# V0p2_Main_PCB2.net
KiCad netlist of a schematic drawn in EAGLE
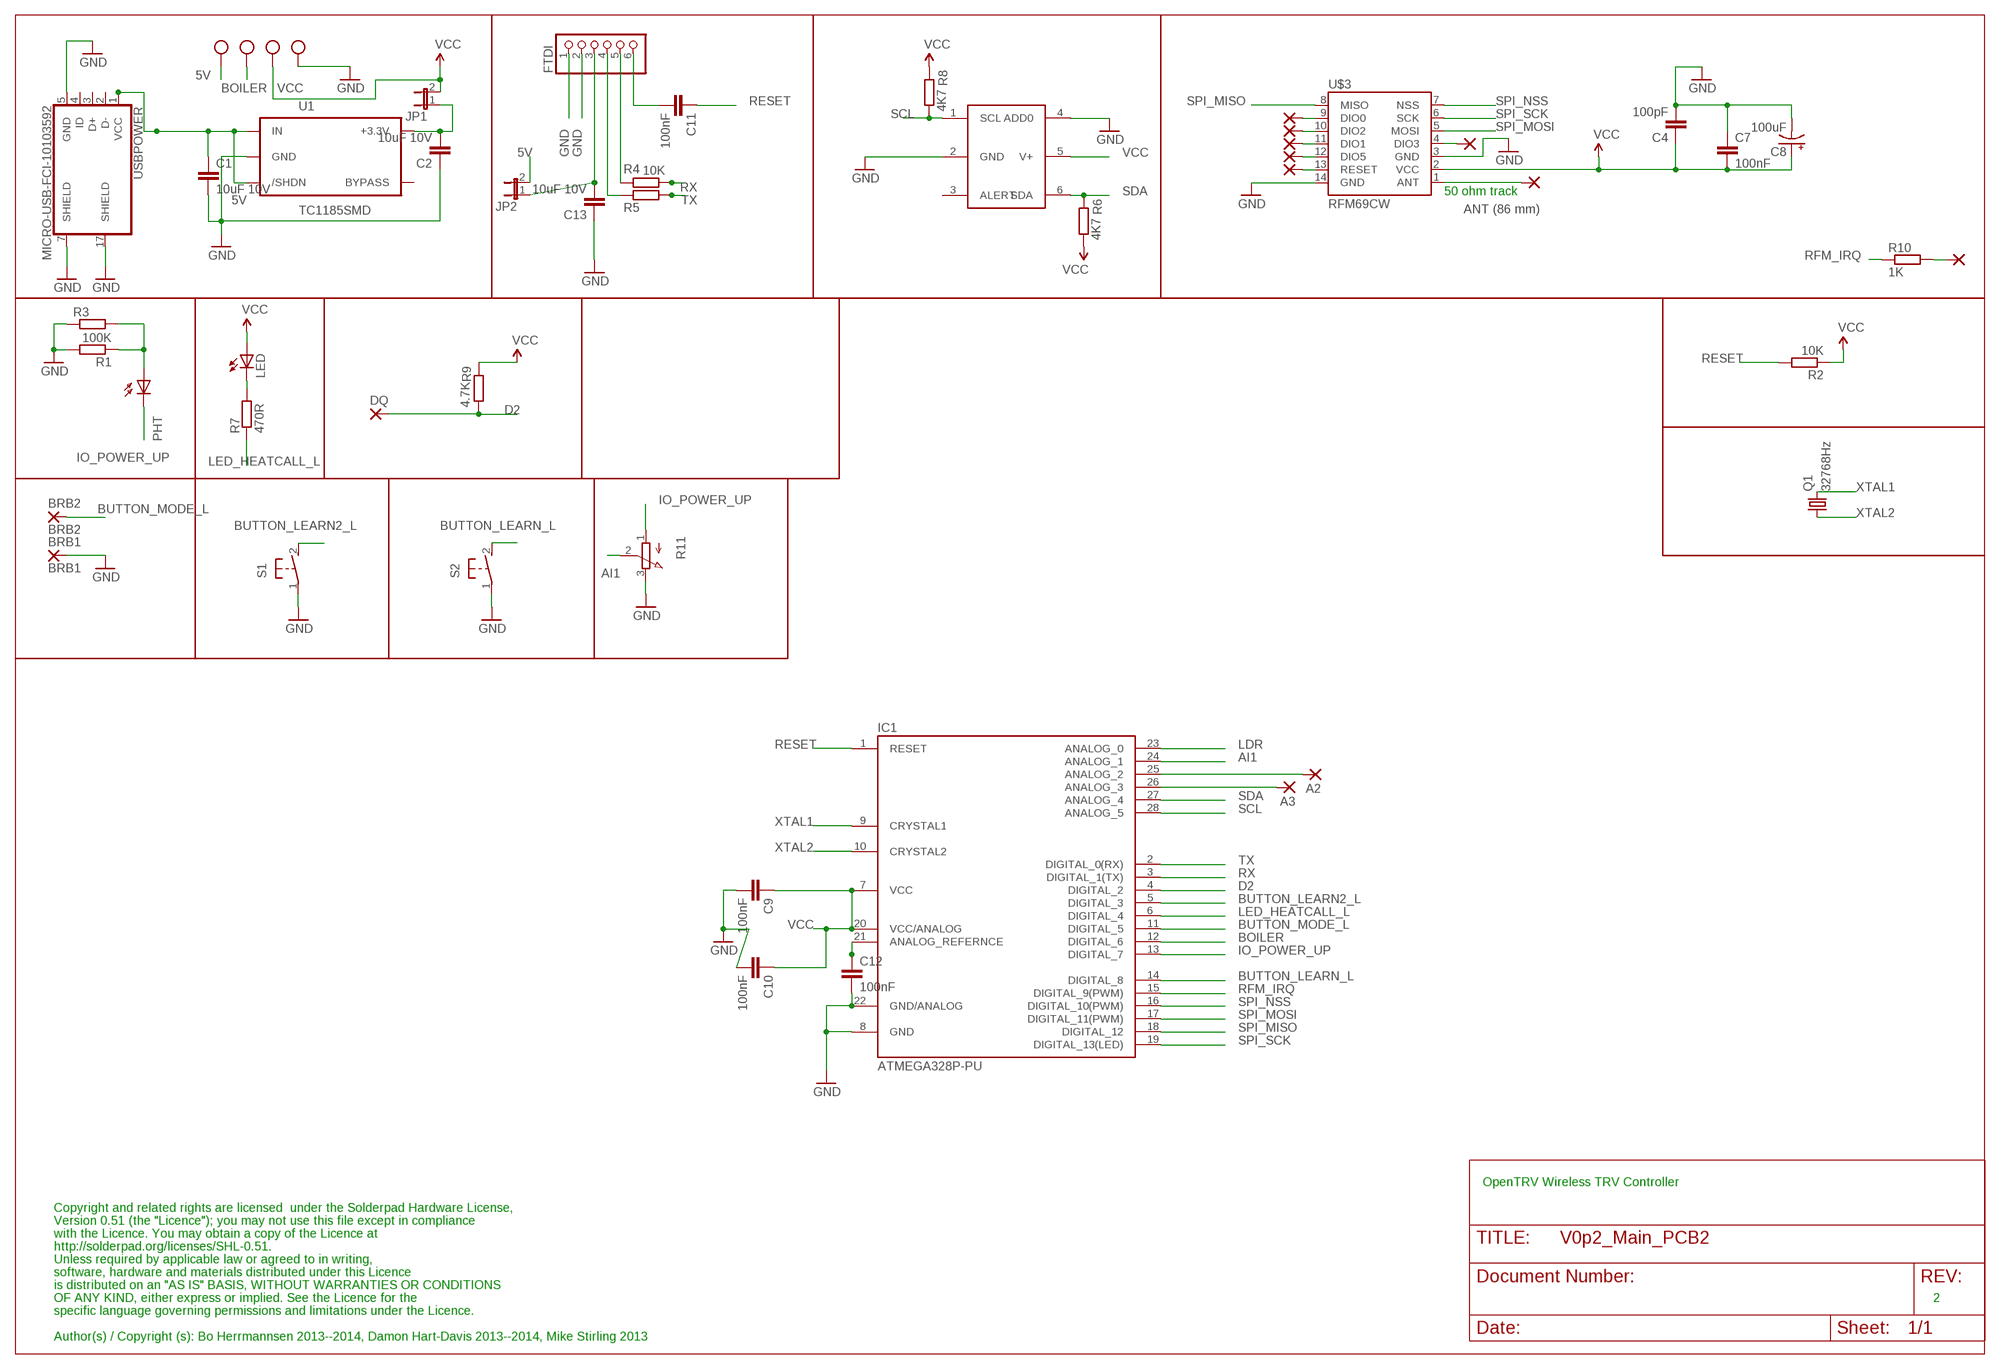
[diagram p0: schematic, sheet 1]

(export (version "E")
  (design (tool "Eeschema 10.0.6"))
  (components
    (comp (ref "A2")
      (value "2,15/1,0")
      (footprint "eagle-import:2,15_1,0")
      (libsource (lib "eagle-import") (part "2,15/1,0"))
    )
    (comp (ref "A3")
      (value "2,15/1,0")
      (footprint "eagle-import:2,15_1,0")
      (libsource (lib "eagle-import") (part "2,15/1,0"))
    )
    (comp (ref "ANT")
      (value "ANT (86 mm)")
      (footprint "eagle-import:2,15_1,0")
      (libsource (lib "eagle-import") (part "2,15/1,0"))
    )
    (comp (ref "BRB1")
      (value "BRB1")
      (footprint "eagle-import:2,15_1,0")
      (libsource (lib "eagle-import") (part "2,15/1,0"))
    )
    (comp (ref "BRB2")
      (value "BRB2")
      (footprint "eagle-import:2,15_1,0")
      (libsource (lib "eagle-import") (part "2,15/1,0"))
    )
    (comp (ref "C1")
      (value "10uF 10V")
      (footprint "eagle-import:C0603")
      (libsource (lib "eagle-import") (part "C-EUC0603"))
    )
    (comp (ref "C2")
      (value "10uF 10V")
      (footprint "eagle-import:C0603")
      (libsource (lib "eagle-import") (part "C-EUC0603"))
    )
    (comp (ref "C4")
      (value "100pF")
      (footprint "eagle-import:C0603")
      (libsource (lib "eagle-import") (part "C-EUC0603"))
    )
    (comp (ref "C7")
      (value "100nF")
      (footprint "eagle-import:C0603")
      (libsource (lib "eagle-import") (part "C-EUC0603"))
    )
    (comp (ref "C8")
      (value "100uF")
      (footprint "eagle-import:EIA3216")
      (libsource (lib "eagle-import") (part "CAP_POL1206"))
    )
    (comp (ref "C9")
      (value "100nF")
      (footprint "eagle-import:C0603")
      (libsource (lib "eagle-import") (part "C-EUC0603"))
    )
    (comp (ref "C10")
      (value "100nF")
      (footprint "eagle-import:C0603")
      (libsource (lib "eagle-import") (part "C-EUC0603"))
    )
    (comp (ref "C11")
      (value "100nF")
      (footprint "eagle-import:C0603")
      (libsource (lib "eagle-import") (part "C-EUC0603"))
    )
    (comp (ref "C12")
      (value "100nF")
      (footprint "eagle-import:C0603")
      (libsource (lib "eagle-import") (part "C-EUC0603"))
    )
    (comp (ref "C13")
      (value "10uF 10V")
      (footprint "eagle-import:C0603")
      (libsource (lib "eagle-import") (part "C-EUC0603"))
    )
    (comp (ref "DIO0")
      (value "ANT (86 mm)")
      (footprint "eagle-import:2,15_1,0")
      (libsource (lib "eagle-import") (part "2,15/1,0"))
    )
    (comp (ref "DIO1")
      (value "ANT (86 mm)")
      (footprint "eagle-import:2,15_1,0")
      (libsource (lib "eagle-import") (part "2,15/1,0"))
    )
    (comp (ref "DIO2")
      (value "ANT (86 mm)")
      (footprint "eagle-import:2,15_1,0")
      (libsource (lib "eagle-import") (part "2,15/1,0"))
    )
    (comp (ref "DIO3")
      (value "ANT (86 mm)")
      (footprint "eagle-import:2,15_1,0")
      (libsource (lib "eagle-import") (part "2,15/1,0"))
    )
    (comp (ref "DIO5")
      (value "ANT (86 mm)")
      (footprint "eagle-import:2,15_1,0")
      (libsource (lib "eagle-import") (part "2,15/1,0"))
    )
    (comp (ref "DQ")
      (value "2,15/1,0")
      (footprint "eagle-import:2,15_1,0")
      (libsource (lib "eagle-import") (part "2,15/1,0"))
    )
    (comp (ref "FTDI")
      (value "PINHD-1X6/90")
      (footprint "eagle-import:1X06_90")
      (libsource (lib "eagle-import") (part "PINHD-1X6/90"))
    )
    (comp (ref "IC1")
      (value "ATMEGA328P-PU")
      (footprint "eagle-import:DIL28-3")
      (libsource (lib "eagle-import") (part "ATMEGA8-PU"))
    )
    (comp (ref "IRQ")
      (value "ANT (86 mm)")
      (footprint "eagle-import:2,15_1,0")
      (libsource (lib "eagle-import") (part "2,15/1,0"))
    )
    (comp (ref "JP1")
      (value "JP1E")
      (footprint "eagle-import:JP1")
      (libsource (lib "eagle-import") (part "JP1E"))
    )
    (comp (ref "JP2")
      (value "JP1E")
      (footprint "eagle-import:JP1")
      (libsource (lib "eagle-import") (part "JP1E"))
    )
    (comp (ref "LED")
      (value "LED3MM")
      (footprint "eagle-import:LED3MM")
      (libsource (lib "eagle-import") (part "LED3MM"))
    )
    (comp (ref "PHT")
      (value "BPX65")
      (footprint "eagle-import:BPX65")
      (fields (field (name "MPN") "BPX65."))
      (libsource (lib "eagle-import") (part "BPX65"))
    )
    (comp (ref "Q1")
      (value "32768Hz")
      (footprint "eagle-import:MC-306")
      (fields (field (name "MPN") "MC-306 60.0KHZ  100PPM ,12.5PF"))
      (libsource (lib "eagle-import") (part "MC-306"))
    )
    (comp (ref "R1")
      (value "100K")
      (footprint "eagle-import:R0603")
      (libsource (lib "eagle-import") (part "R-EU_R0603"))
    )
    (comp (ref "R2")
      (value "10K")
      (footprint "eagle-import:R0603")
      (libsource (lib "eagle-import") (part "R-EU_R0603"))
    )
    (comp (ref "R3")
      (value "R-EU_0309/V")
      (footprint "eagle-import:0309V")
      (libsource (lib "eagle-import") (part "R-EU_0309/V"))
    )
    (comp (ref "R4")
      (value "10K")
      (footprint "eagle-import:R0603")
      (libsource (lib "eagle-import") (part "R-EU_R0603"))
    )
    (comp (ref "R5")
      (value "10K")
      (footprint "eagle-import:R0603")
      (libsource (lib "eagle-import") (part "R-EU_R0603"))
    )
    (comp (ref "R6")
      (value "4K7")
      (footprint "eagle-import:R0603")
      (libsource (lib "eagle-import") (part "R-EU_R0603"))
    )
    (comp (ref "R7")
      (value "470R")
      (footprint "eagle-import:R0603")
      (libsource (lib "eagle-import") (part "R-EU_R0603"))
    )
    (comp (ref "R8")
      (value "4K7")
      (footprint "eagle-import:R0603")
      (libsource (lib "eagle-import") (part "R-EU_R0603"))
    )
    (comp (ref "R9")
      (value "4.7K")
      (footprint "eagle-import:R0603")
      (libsource (lib "eagle-import") (part "R-EU_R0603"))
    )
    (comp (ref "R10")
      (value "1K")
      (footprint "eagle-import:R0603")
      (libsource (lib "eagle-import") (part "R-EU_R0603"))
    )
    (comp (ref "R11")
      (value "EVUE2A")
      (footprint "eagle-import:EVUE")
      (libsource (lib "eagle-import") (part "EVUE2A"))
    )
    (comp (ref "RST")
      (value "ANT (86 mm)")
      (footprint "eagle-import:2,15_1,0")
      (libsource (lib "eagle-import") (part "2,15/1,0"))
    )
    (comp (ref "S1")
      (value "31-XX")
      (footprint "eagle-import:B3F-31XX")
      (libsource (lib "eagle-import") (part "31-XX"))
    )
    (comp (ref "S2")
      (value "31-XX")
      (footprint "eagle-import:B3F-31XX")
      (libsource (lib "eagle-import") (part "31-XX"))
    )
    (comp (ref "TMP1")
      (value "TMP1")
      (footprint "eagle-import:TMP112")
      (libsource (lib "eagle-import") (part "TMP112"))
    )
    (comp (ref "U$3")
      (value "RFM69CW")
      (footprint "eagle-import:RFM69")
      (libsource (lib "eagle-import") (part "RFM69SMD"))
    )
    (comp (ref "U1")
      (value "TC1185SMD")
      (footprint "eagle-import:TC1185")
      (libsource (lib "eagle-import") (part "TC1185SMD"))
    )
    (comp (ref "USBPOWER")
      (value "MICRO-USB-FCI-10103592")
      (footprint "eagle-import:MICRO-USB-FCI-10103592")
      (libsource (lib "eagle-import") (part "MICRO-USB-FCI-10103592"))
    )
    (comp (ref "X1")
      (value "W237-102")
      (footprint "eagle-import:SCREWTERMINAL")
      (fields (field (name "MPN") "237-102"))
      (libsource (lib "eagle-import") (part "W237-102"))
    )
    (comp (ref "X2")
      (value "W237-102")
      (footprint "eagle-import:SCREWTERMINAL")
      (fields (field (name "MPN") "237-102"))
      (libsource (lib "eagle-import") (part "W237-102"))
    )
  )
  (nets
    (net (code "1") (name "/5V") (class "Default")
      (node (ref "C1") (pin "1") (pinfunction "1_1") (pintype "passive"))
      (node (ref "JP2") (pin "2") (pinfunction "2_2") (pintype "passive"))
      (node (ref "U1") (pin "1") (pinfunction "IN_1") (pintype "passive"))
      (node (ref "U1") (pin "3") (pinfunction "/SHDN_3") (pintype "passive"))
      (node (ref "USBPOWER") (pin "1") (pinfunction "VCC_1") (pintype "bidirectional"))
      (node (ref "X1") (pin "2") (pinfunction "KL_2") (pintype "passive"))
    )
    (net (code "2") (name "/AI1") (class "Default")
      (node (ref "IC1") (pin "24") (pinfunction "ANALOG_1_24") (pintype "bidirectional"))
      (node (ref "R11") (pin "2") (pinfunction "S_2") (pintype "passive"))
    )
    (net (code "3") (name "/BOILER") (class "Default")
      (node (ref "IC1") (pin "12") (pinfunction "DIGITAL_6_12") (pintype "bidirectional"))
      (node (ref "X1") (pin "1") (pinfunction "KL_1") (pintype "passive"))
    )
    (net (code "4") (name "/BUTTON_LEARN2_L") (class "Default")
      (node (ref "IC1") (pin "5") (pinfunction "DIGITAL_3_5") (pintype "bidirectional"))
      (node (ref "S1") (pin "2") (pinfunction "S_2") (pintype "passive"))
    )
    (net (code "5") (name "/BUTTON_LEARN_L") (class "Default")
      (node (ref "IC1") (pin "14") (pinfunction "DIGITAL_8_14") (pintype "bidirectional"))
      (node (ref "S2") (pin "2") (pinfunction "S_2") (pintype "passive"))
    )
    (net (code "6") (name "/BUTTON_MODE_L") (class "Default")
      (node (ref "BRB2") (pin "1") (pinfunction "P_1") (pintype "passive"))
      (node (ref "IC1") (pin "11") (pinfunction "DIGITAL_5_11") (pintype "bidirectional"))
    )
    (net (code "7") (name "/D2") (class "Default")
      (node (ref "DQ") (pin "1") (pinfunction "P_1") (pintype "passive"))
      (node (ref "IC1") (pin "4") (pinfunction "DIGITAL_2_4") (pintype "bidirectional"))
      (node (ref "R9") (pin "1") (pinfunction "1_1") (pintype "passive"))
    )
    (net (code "8") (name "/IO_POWER_UP") (class "Default")
      (node (ref "IC1") (pin "13") (pinfunction "DIGITAL_7_13") (pintype "bidirectional"))
      (node (ref "PHT") (pin "K") (pinfunction "C_K") (pintype "passive"))
      (node (ref "R11") (pin "1") (pinfunction "A_1") (pintype "passive"))
    )
    (net (code "9") (name "/LDR") (class "Default")
      (node (ref "IC1") (pin "23") (pinfunction "ANALOG_0_23") (pintype "bidirectional"))
      (node (ref "PHT") (pin "A") (pinfunction "A_A") (pintype "passive"))
      (node (ref "R1") (pin "1") (pinfunction "1_1") (pintype "passive"))
      (node (ref "R3") (pin "2") (pinfunction "2_2") (pintype "passive"))
    )
    (net (code "10") (name "/LED_HEATCALL_L") (class "Default")
      (node (ref "IC1") (pin "6") (pinfunction "DIGITAL_4_6") (pintype "bidirectional"))
      (node (ref "R7") (pin "1") (pinfunction "1_1") (pintype "passive"))
    )
    (net (code "11") (name "/RESET") (class "Default")
      (node (ref "C11") (pin "1") (pinfunction "1_1") (pintype "passive"))
      (node (ref "IC1") (pin "1") (pinfunction "RESET_1") (pintype "bidirectional"))
      (node (ref "R2") (pin "2") (pinfunction "2_2") (pintype "passive"))
    )
    (net (code "12") (name "/RFM_IRQ") (class "Default")
      (node (ref "IC1") (pin "15") (pinfunction "DIGITAL_9(PWM)_15") (pintype "bidirectional"))
      (node (ref "R10") (pin "1") (pinfunction "1_1") (pintype "passive"))
    )
    (net (code "13") (name "/RX") (class "Default")
      (node (ref "IC1") (pin "3") (pinfunction "DIGITAL_1(TX)_3") (pintype "bidirectional"))
      (node (ref "R4") (pin "1") (pinfunction "1_1") (pintype "passive"))
    )
    (net (code "14") (name "/SCL") (class "Default")
      (node (ref "IC1") (pin "28") (pinfunction "ANALOG_5_28") (pintype "bidirectional"))
      (node (ref "R8") (pin "1") (pinfunction "1_1") (pintype "passive"))
      (node (ref "TMP1") (pin "1") (pinfunction "SCL_1") (pintype "bidirectional"))
    )
    (net (code "15") (name "/SDA") (class "Default")
      (node (ref "IC1") (pin "27") (pinfunction "ANALOG_4_27") (pintype "bidirectional"))
      (node (ref "R6") (pin "2") (pinfunction "2_2") (pintype "passive"))
      (node (ref "TMP1") (pin "6") (pinfunction "SDA_6") (pintype "bidirectional"))
    )
    (net (code "16") (name "/SPI_MISO") (class "Default")
      (node (ref "IC1") (pin "18") (pinfunction "DIGITAL_12_18") (pintype "bidirectional"))
      (node (ref "U$3") (pin "8") (pinfunction "MISO_8") (pintype "input"))
    )
    (net (code "17") (name "/SPI_MOSI") (class "Default")
      (node (ref "IC1") (pin "17") (pinfunction "DIGITAL_11(PWM)_17") (pintype "bidirectional"))
      (node (ref "U$3") (pin "5") (pinfunction "MOSI_5") (pintype "input"))
    )
    (net (code "18") (name "/SPI_NSS") (class "Default")
      (node (ref "IC1") (pin "16") (pinfunction "DIGITAL_10(PWM)_16") (pintype "bidirectional"))
      (node (ref "U$3") (pin "7") (pinfunction "NSS_7") (pintype "output"))
    )
    (net (code "19") (name "/SPI_SCK") (class "Default")
      (node (ref "IC1") (pin "19") (pinfunction "DIGITAL_13(LED)_19") (pintype "bidirectional"))
      (node (ref "U$3") (pin "6") (pinfunction "SCK_6") (pintype "input"))
    )
    (net (code "20") (name "/TX") (class "Default")
      (node (ref "IC1") (pin "2") (pinfunction "DIGITAL_0(RX)_2") (pintype "bidirectional"))
      (node (ref "R5") (pin "1") (pinfunction "1_1") (pintype "passive"))
    )
    (net (code "21") (name "/XTAL1") (class "Default")
      (node (ref "IC1") (pin "9") (pinfunction "CRYSTAL1_9") (pintype "bidirectional"))
      (node (ref "Q1") (pin "4") (pinfunction "2_4") (pintype "passive"))
    )
    (net (code "22") (name "/XTAL2") (class "Default")
      (node (ref "IC1") (pin "10") (pinfunction "CRYSTAL2_10") (pintype "bidirectional"))
      (node (ref "Q1") (pin "1") (pinfunction "1_1") (pintype "passive"))
    )
    (net (code "23") (name "GND") (class "Default")
      (node (ref "BRB1") (pin "1") (pinfunction "P_1") (pintype "passive"))
      (node (ref "C1") (pin "2") (pinfunction "2_2") (pintype "passive"))
      (node (ref "C10") (pin "2") (pinfunction "2_2") (pintype "passive"))
      (node (ref "C12") (pin "2") (pinfunction "2_2") (pintype "passive"))
      (node (ref "C13") (pin "1") (pinfunction "1_1") (pintype "passive"))
      (node (ref "C2") (pin "1") (pinfunction "1_1") (pintype "passive"))
      (node (ref "C4") (pin "2") (pinfunction "2_2") (pintype "passive"))
      (node (ref "C7") (pin "1") (pinfunction "1_1") (pintype "passive"))
      (node (ref "C8") (pin "C") (pinfunction "-_C") (pintype "passive"))
      (node (ref "C9") (pin "2") (pinfunction "2_2") (pintype "passive"))
      (node (ref "FTDI") (pin "1") (pinfunction "1_1") (pintype "passive"))
      (node (ref "FTDI") (pin "2") (pinfunction "2_2") (pintype "passive"))
      (node (ref "IC1") (pin "22") (pinfunction "GND/ANALOG_22") (pintype "power_in"))
      (node (ref "IC1") (pin "8") (pinfunction "GND_8") (pintype "power_in"))
      (node (ref "R1") (pin "2") (pinfunction "2_2") (pintype "passive"))
      (node (ref "R11") (pin "3") (pinfunction "E_3") (pintype "passive"))
      (node (ref "R3") (pin "1") (pinfunction "1_1") (pintype "passive"))
      (node (ref "S1") (pin "1") (pinfunction "P_1") (pintype "passive"))
      (node (ref "S2") (pin "1") (pinfunction "P_1") (pintype "passive"))
      (node (ref "TMP1") (pin "2") (pinfunction "GND_2") (pintype "bidirectional"))
      (node (ref "TMP1") (pin "4") (pinfunction "ADD0_4") (pintype "bidirectional"))
      (node (ref "U$3") (pin "14") (pinfunction "GND_14") (pintype "power_in"))
      (node (ref "U$3") (pin "3") (pinfunction "GND_3") (pintype "power_in"))
      (node (ref "U1") (pin "2") (pinfunction "GND_2") (pintype "passive"))
      (node (ref "USBPOWER") (pin "17") (pinfunction "SHIELD_17") (pintype "bidirectional"))
      (node (ref "USBPOWER") (pin "5") (pinfunction "GND_5") (pintype "bidirectional"))
      (node (ref "USBPOWER") (pin "7") (pinfunction "SHIELD_7") (pintype "bidirectional"))
      (node (ref "X2") (pin "2") (pinfunction "KL_2") (pintype "passive"))
    )
    (net (code "24") (name "Net-(A2-P)") (class "Default")
      (node (ref "A2") (pin "1") (pinfunction "P_1") (pintype "passive"))
      (node (ref "IC1") (pin "25") (pinfunction "ANALOG_2_25") (pintype "bidirectional"))
    )
    (net (code "25") (name "Net-(A3-P)") (class "Default")
      (node (ref "A3") (pin "1") (pinfunction "P_1") (pintype "passive"))
      (node (ref "IC1") (pin "26") (pinfunction "ANALOG_3_26") (pintype "bidirectional"))
    )
    (net (code "26") (name "Net-(ANT-P)") (class "Default")
      (node (ref "ANT") (pin "1") (pinfunction "P_1") (pintype "passive"))
      (node (ref "U$3") (pin "1") (pinfunction "ANT_1") (pintype "bidirectional"))
    )
    (net (code "27") (name "Net-(C11-Pad2)") (class "Default")
      (node (ref "C11") (pin "2") (pinfunction "2_2") (pintype "passive"))
      (node (ref "FTDI") (pin "6") (pinfunction "6_6") (pintype "passive"))
    )
    (net (code "28") (name "Net-(C13-Pad2)") (class "Default")
      (node (ref "C13") (pin "2") (pinfunction "2_2") (pintype "passive"))
      (node (ref "FTDI") (pin "3") (pinfunction "3_3") (pintype "passive"))
      (node (ref "JP2") (pin "1") (pinfunction "1_1") (pintype "passive"))
    )
    (net (code "29") (name "Net-(DIO0-P)") (class "Default")
      (node (ref "DIO0") (pin "1") (pinfunction "P_1") (pintype "passive"))
      (node (ref "U$3") (pin "9") (pinfunction "DIO0_9") (pintype "output"))
    )
    (net (code "30") (name "Net-(DIO1-P)") (class "Default")
      (node (ref "DIO1") (pin "1") (pinfunction "P_1") (pintype "passive"))
      (node (ref "U$3") (pin "11") (pinfunction "DIO1_11") (pintype "input"))
    )
    (net (code "31") (name "Net-(DIO2-P)") (class "Default")
      (node (ref "DIO2") (pin "1") (pinfunction "P_1") (pintype "passive"))
      (node (ref "U$3") (pin "10") (pinfunction "DIO2_10") (pintype "input"))
    )
    (net (code "32") (name "Net-(DIO3-P)") (class "Default")
      (node (ref "DIO3") (pin "1") (pinfunction "P_1") (pintype "passive"))
      (node (ref "U$3") (pin "4") (pinfunction "DIO3_4") (pintype "input"))
    )
    (net (code "33") (name "Net-(DIO5-P)") (class "Default")
      (node (ref "DIO5") (pin "1") (pinfunction "P_1") (pintype "passive"))
      (node (ref "U$3") (pin "12") (pinfunction "DIO5_12") (pintype "input"))
    )
    (net (code "34") (name "Net-(FTDI-Pad4)") (class "Default")
      (node (ref "FTDI") (pin "4") (pinfunction "4_4") (pintype "passive"))
      (node (ref "R5") (pin "2") (pinfunction "2_2") (pintype "passive"))
    )
    (net (code "35") (name "Net-(FTDI-Pad5)") (class "Default")
      (node (ref "FTDI") (pin "5") (pinfunction "5_5") (pintype "passive"))
      (node (ref "R4") (pin "2") (pinfunction "2_2") (pintype "passive"))
    )
    (net (code "36") (name "Net-(IC1-ANALOG_REFERNCE)") (class "Default")
      (node (ref "C12") (pin "1") (pinfunction "1_1") (pintype "passive"))
      (node (ref "IC1") (pin "21") (pinfunction "ANALOG_REFERNCE_21") (pintype "passive"))
    )
    (net (code "37") (name "Net-(IRQ-P)") (class "Default")
      (node (ref "IRQ") (pin "1") (pinfunction "P_1") (pintype "passive"))
      (node (ref "R10") (pin "2") (pinfunction "2_2") (pintype "passive"))
    )
    (net (code "38") (name "Net-(LED-C)") (class "Default")
      (node (ref "LED") (pin "K") (pinfunction "C_K") (pintype "passive"))
      (node (ref "R7") (pin "2") (pinfunction "2_2") (pintype "passive"))
    )
    (net (code "39") (name "Net-(RST-P)") (class "Default")
      (node (ref "RST") (pin "1") (pinfunction "P_1") (pintype "passive"))
      (node (ref "U$3") (pin "13") (pinfunction "RESET_13") (pintype "power_in"))
    )
    (net (code "40") (name "Net-(U1-+3.3V)") (class "Default")
      (node (ref "C2") (pin "2") (pinfunction "2_2") (pintype "passive"))
      (node (ref "JP1") (pin "1") (pinfunction "1_1") (pintype "passive"))
      (node (ref "U1") (pin "5") (pinfunction "+3.3V_5") (pintype "power_in"))
    )
    (net (code "41") (name "VCC") (class "Default")
      (node (ref "C10") (pin "1") (pinfunction "1_1") (pintype "passive"))
      (node (ref "C4") (pin "1") (pinfunction "1_1") (pintype "passive"))
      (node (ref "C7") (pin "2") (pinfunction "2_2") (pintype "passive"))
      (node (ref "C8") (pin "A") (pinfunction "+_A") (pintype "passive"))
      (node (ref "C9") (pin "1") (pinfunction "1_1") (pintype "passive"))
      (node (ref "IC1") (pin "20") (pinfunction "VCC/ANALOG_20") (pintype "passive"))
      (node (ref "IC1") (pin "7") (pinfunction "VCC_7") (pintype "power_in"))
      (node (ref "JP1") (pin "2") (pinfunction "2_2") (pintype "passive"))
      (node (ref "LED") (pin "A") (pinfunction "A_A") (pintype "passive"))
      (node (ref "R2") (pin "1") (pinfunction "1_1") (pintype "passive"))
      (node (ref "R6") (pin "1") (pinfunction "1_1") (pintype "passive"))
      (node (ref "R8") (pin "2") (pinfunction "2_2") (pintype "passive"))
      (node (ref "R9") (pin "2") (pinfunction "2_2") (pintype "passive"))
      (node (ref "TMP1") (pin "5") (pinfunction "V+_5") (pintype "bidirectional"))
      (node (ref "U$3") (pin "2") (pinfunction "VCC_2") (pintype "bidirectional"))
      (node (ref "X2") (pin "1") (pinfunction "KL_1") (pintype "passive"))
    )
    (net (code "42") (name "unconnected-(TMP1-ALERT-Pad3)") (class "Default")
      (node (ref "TMP1") (pin "3") (pinfunction "ALERT_3") (pintype "bidirectional"))
    )
    (net (code "43") (name "unconnected-(U1-BYPASS-Pad4)") (class "Default")
      (node (ref "U1") (pin "4") (pinfunction "BYPASS_4") (pintype "passive"))
    )
    (net (code "44") (name "unconnected-(USBPOWER-D+-Pad3)") (class "Default")
      (node (ref "USBPOWER") (pin "3") (pinfunction "D+_3") (pintype "bidirectional"))
    )
    (net (code "45") (name "unconnected-(USBPOWER-D--Pad2)") (class "Default")
      (node (ref "USBPOWER") (pin "2") (pinfunction "D-_2") (pintype "bidirectional"))
    )
    (net (code "46") (name "unconnected-(USBPOWER-ID-Pad4)") (class "Default")
      (node (ref "USBPOWER") (pin "4") (pinfunction "ID_4") (pintype "bidirectional"))
    )
  )
)
